# 3_Proxy.net
KiCad netlist of a schematic drawn in Altium Designer
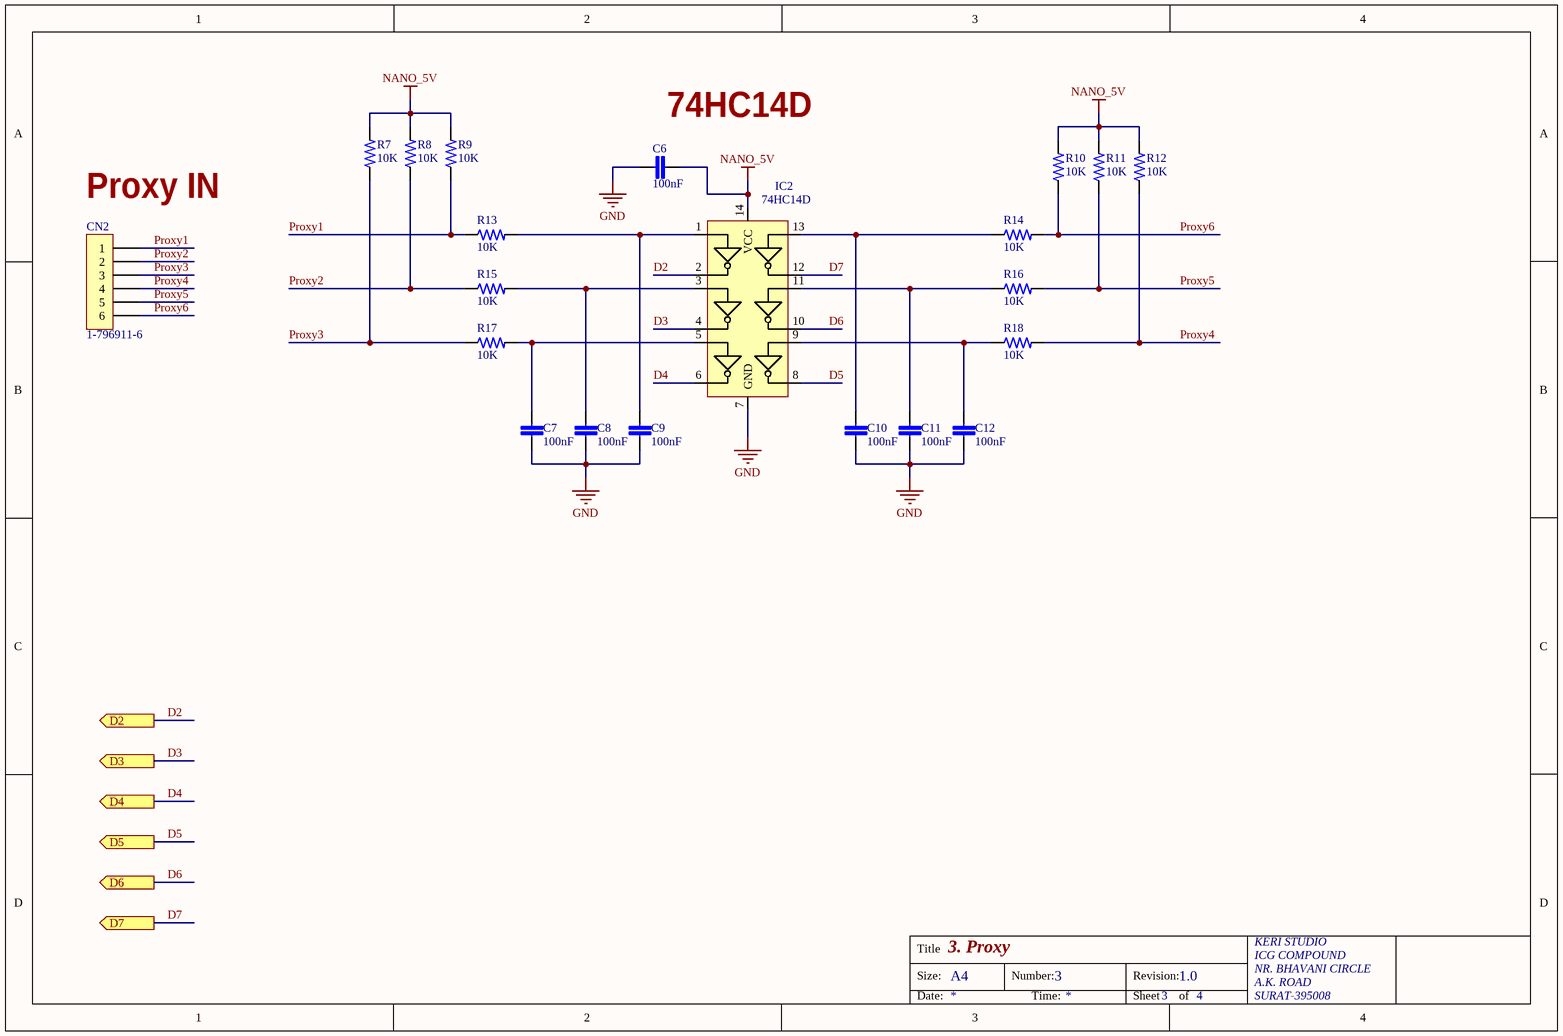
[diagram p0: 3. Proxy.SchDoc]

(export (version "E")
  (design (tool "Eeschema 10.0.6"))
  (components
    (comp (ref "C6")
      (value "100nF")
      (footprint "C0805")
      (description "Multilayer Ceramic Capacitors MLCC - SMD/SMT 0805 0.1uF 50volts X7R 20%")
      (fields
        (field (name "MANUFACTURER") "Murata")
        (field (name "MANUFACTURER PART NUMBER") "GCJ21BR71H104MA01L")
      )
      (libsource (lib "") (part "C_0805_0.1uF_1"))
    )
    (comp (ref "C7")
      (value "100nF")
      (footprint "C0805")
      (description "Multilayer Ceramic Capacitors MLCC - SMD/SMT 0805 0.1uF 50volts X7R 20%")
      (fields
        (field (name "MANUFACTURER") "Murata")
        (field (name "MANUFACTURER PART NUMBER") "GCJ21BR71H104MA01L")
      )
      (libsource (lib "keri_lib") (part "C_0805_0.1uF"))
    )
    (comp (ref "C8")
      (value "100nF")
      (footprint "C0805")
      (description "Multilayer Ceramic Capacitors MLCC - SMD/SMT 0805 0.1uF 50volts X7R 20%")
      (fields
        (field (name "MANUFACTURER") "Murata")
        (field (name "MANUFACTURER PART NUMBER") "GCJ21BR71H104MA01L")
      )
      (libsource (lib "keri_lib") (part "C_0805_0.1uF"))
    )
    (comp (ref "C9")
      (value "100nF")
      (footprint "C0805")
      (description "Multilayer Ceramic Capacitors MLCC - SMD/SMT 0805 0.1uF 50volts X7R 20%")
      (fields
        (field (name "MANUFACTURER") "Murata")
        (field (name "MANUFACTURER PART NUMBER") "GCJ21BR71H104MA01L")
      )
      (libsource (lib "keri_lib") (part "C_0805_0.1uF"))
    )
    (comp (ref "C10")
      (value "100nF")
      (footprint "C0805")
      (description "Multilayer Ceramic Capacitors MLCC - SMD/SMT 0805 0.1uF 50volts X7R 20%")
      (fields
        (field (name "MANUFACTURER") "Murata")
        (field (name "MANUFACTURER PART NUMBER") "GCJ21BR71H104MA01L")
      )
      (libsource (lib "keri_lib") (part "C_0805_0.1uF"))
    )
    (comp (ref "C11")
      (value "100nF")
      (footprint "C0805")
      (description "Multilayer Ceramic Capacitors MLCC - SMD/SMT 0805 0.1uF 50volts X7R 20%")
      (fields
        (field (name "MANUFACTURER") "Murata")
        (field (name "MANUFACTURER PART NUMBER") "GCJ21BR71H104MA01L")
      )
      (libsource (lib "keri_lib") (part "C_0805_0.1uF"))
    )
    (comp (ref "C12")
      (value "100nF")
      (footprint "C0805")
      (description "Multilayer Ceramic Capacitors MLCC - SMD/SMT 0805 0.1uF 50volts X7R 20%")
      (fields
        (field (name "MANUFACTURER") "Murata")
        (field (name "MANUFACTURER PART NUMBER") "GCJ21BR71H104MA01L")
      )
      (libsource (lib "keri_lib") (part "C_0805_0.1uF"))
    )
    (comp (ref "CN2")
      (value "1-796911-6")
      (footprint "Terminal_5.08mm_1X06")
      (description "Conn Terminal Block 16 POS 5mm Solder ST Thru-Hole")
      (fields (field (name "MANUFACTURER") "TE Connectivity") (field (name "VOLTAGE") "300V"))
      (libsource (lib "keri_lib") (part "Terminal_5.08mm_1X06"))
    )
    (comp (ref "IC2")
      (value "74HC14D")
      (footprint "SOIC-14")
      (description "IC, HEX INVERTER, SCHMITT TRIGGER SOIC14")
      (fields
        (field (name "MANUFACTURER") "NXP Semiconductors")
        (field (name "MANUFACTURER PART NUMBER") "74HC14D,653")
      )
      (libsource (lib "keri_lib") (part "74HC14D"))
    )
    (comp (ref "R7")
      (value "10K")
      (footprint "R0805")
      (description "Thick Film Resistors - SMD 10K 0805 5%")
      (fields (field (name "MANUFACTURER") "Bourns") (field (name "TOLERANCE") "5%"))
      (libsource (lib "keri_lib") (part "R_0805_10K"))
    )
    (comp (ref "R8")
      (value "10K")
      (footprint "R0805")
      (description "Thick Film Resistors - SMD 10K 0805 5%")
      (fields (field (name "MANUFACTURER") "Bourns") (field (name "TOLERANCE") "5%"))
      (libsource (lib "keri_lib") (part "R_0805_10K"))
    )
    (comp (ref "R9")
      (value "10K")
      (footprint "R0805")
      (description "Thick Film Resistors - SMD 10K 0805 5%")
      (fields (field (name "MANUFACTURER") "Bourns") (field (name "TOLERANCE") "5%"))
      (libsource (lib "keri_lib") (part "R_0805_10K"))
    )
    (comp (ref "R10")
      (value "10K")
      (footprint "R0805")
      (description "Thick Film Resistors - SMD 10K 0805 5%")
      (fields (field (name "MANUFACTURER") "Bourns") (field (name "TOLERANCE") "5%"))
      (libsource (lib "keri_lib") (part "R_0805_10K"))
    )
    (comp (ref "R11")
      (value "10K")
      (footprint "R0805")
      (description "Thick Film Resistors - SMD 10K 0805 5%")
      (fields (field (name "MANUFACTURER") "Bourns") (field (name "TOLERANCE") "5%"))
      (libsource (lib "keri_lib") (part "R_0805_10K"))
    )
    (comp (ref "R12")
      (value "10K")
      (footprint "R0805")
      (description "Thick Film Resistors - SMD 10K 0805 5%")
      (fields (field (name "MANUFACTURER") "Bourns") (field (name "TOLERANCE") "5%"))
      (libsource (lib "keri_lib") (part "R_0805_10K"))
    )
    (comp (ref "R13")
      (value "10K")
      (footprint "R0805")
      (description "Thick Film Resistors - SMD 10K 0805 5%")
      (fields (field (name "MANUFACTURER") "Bourns") (field (name "TOLERANCE") "5%"))
      (libsource (lib "keri_lib") (part "R_0805_10K"))
    )
    (comp (ref "R14")
      (value "10K")
      (footprint "R0805")
      (description "Thick Film Resistors - SMD 10K 0805 5%")
      (fields (field (name "MANUFACTURER") "Bourns") (field (name "TOLERANCE") "5%"))
      (libsource (lib "keri_lib") (part "R_0805_10K"))
    )
    (comp (ref "R15")
      (value "10K")
      (footprint "R0805")
      (description "Thick Film Resistors - SMD 10K 0805 5%")
      (fields (field (name "MANUFACTURER") "Bourns") (field (name "TOLERANCE") "5%"))
      (libsource (lib "keri_lib") (part "R_0805_10K"))
    )
    (comp (ref "R16")
      (value "10K")
      (footprint "R0805")
      (description "Thick Film Resistors - SMD 10K 0805 5%")
      (fields (field (name "MANUFACTURER") "Bourns") (field (name "TOLERANCE") "5%"))
      (libsource (lib "keri_lib") (part "R_0805_10K"))
    )
    (comp (ref "R17")
      (value "10K")
      (footprint "R0805")
      (description "Thick Film Resistors - SMD 10K 0805 5%")
      (fields (field (name "MANUFACTURER") "Bourns") (field (name "TOLERANCE") "5%"))
      (libsource (lib "keri_lib") (part "R_0805_10K"))
    )
    (comp (ref "R18")
      (value "10K")
      (footprint "R0805")
      (description "Thick Film Resistors - SMD 10K 0805 5%")
      (fields (field (name "MANUFACTURER") "Bourns") (field (name "TOLERANCE") "5%"))
      (libsource (lib "keri_lib") (part "R_0805_10K"))
    )
  )
  (nets
    (net (code "1") (name "/D2") (class "Default")
      (node (ref "IC2") (pin "2") (pinfunction "1Y_2") (pintype "passive"))
    )
    (net (code "2") (name "/D3") (class "Default")
      (node (ref "IC2") (pin "4") (pinfunction "2Y_4") (pintype "passive"))
    )
    (net (code "3") (name "/D4") (class "Default")
      (node (ref "IC2") (pin "6") (pinfunction "3Y_6") (pintype "passive"))
    )
    (net (code "4") (name "/D5") (class "Default")
      (node (ref "IC2") (pin "8") (pinfunction "4Y_8") (pintype "passive"))
    )
    (net (code "5") (name "/D6") (class "Default")
      (node (ref "IC2") (pin "10") (pinfunction "5Y_10") (pintype "passive"))
    )
    (net (code "6") (name "/D7") (class "Default")
      (node (ref "IC2") (pin "12") (pinfunction "6Y_12") (pintype "passive"))
    )
    (net (code "7") (name "/Proxy1") (class "Default")
      (node (ref "CN2") (pin "1") (pinfunction "1_1") (pintype "passive"))
      (node (ref "R13") (pin "1") (pinfunction "1_1") (pintype "passive"))
      (node (ref "R9") (pin "1") (pinfunction "1_1") (pintype "passive"))
    )
    (net (code "8") (name "/Proxy2") (class "Default")
      (node (ref "CN2") (pin "2") (pinfunction "2_2") (pintype "passive"))
      (node (ref "R15") (pin "1") (pinfunction "1_1") (pintype "passive"))
      (node (ref "R8") (pin "1") (pinfunction "1_1") (pintype "passive"))
    )
    (net (code "9") (name "/Proxy3") (class "Default")
      (node (ref "CN2") (pin "3") (pinfunction "3_3") (pintype "passive"))
      (node (ref "R17") (pin "1") (pinfunction "1_1") (pintype "passive"))
      (node (ref "R7") (pin "1") (pinfunction "1_1") (pintype "passive"))
    )
    (net (code "10") (name "/Proxy4") (class "Default")
      (node (ref "CN2") (pin "4") (pinfunction "4_4") (pintype "passive"))
      (node (ref "R12") (pin "1") (pinfunction "1_1") (pintype "passive"))
      (node (ref "R18") (pin "2") (pinfunction "2_2") (pintype "passive"))
    )
    (net (code "11") (name "/Proxy5") (class "Default")
      (node (ref "CN2") (pin "5") (pinfunction "5_5") (pintype "passive"))
      (node (ref "R11") (pin "1") (pinfunction "1_1") (pintype "passive"))
      (node (ref "R16") (pin "2") (pinfunction "2_2") (pintype "passive"))
    )
    (net (code "12") (name "/Proxy6") (class "Default")
      (node (ref "CN2") (pin "6") (pinfunction "6_6") (pintype "passive"))
      (node (ref "R10") (pin "1") (pinfunction "1_1") (pintype "passive"))
      (node (ref "R14") (pin "2") (pinfunction "2_2") (pintype "passive"))
    )
    (net (code "13") (name "GND") (class "Default")
      (node (ref "C10") (pin "2") (pinfunction "2_2") (pintype "passive"))
      (node (ref "C11") (pin "2") (pinfunction "2_2") (pintype "passive"))
      (node (ref "C12") (pin "2") (pinfunction "2_2") (pintype "passive"))
      (node (ref "C6") (pin "2") (pinfunction "2_2") (pintype "passive"))
      (node (ref "C7") (pin "2") (pinfunction "2_2") (pintype "passive"))
      (node (ref "C8") (pin "2") (pinfunction "2_2") (pintype "passive"))
      (node (ref "C9") (pin "2") (pinfunction "2_2") (pintype "passive"))
      (node (ref "IC2") (pin "7") (pinfunction "GND_7") (pintype "passive"))
    )
    (net (code "14") (name "NANO_5V") (class "Default")
      (node (ref "C6") (pin "1") (pinfunction "1_1") (pintype "passive"))
      (node (ref "IC2") (pin "14") (pinfunction "VCC_14") (pintype "passive"))
      (node (ref "R10") (pin "2") (pinfunction "2_2") (pintype "passive"))
      (node (ref "R11") (pin "2") (pinfunction "2_2") (pintype "passive"))
      (node (ref "R12") (pin "2") (pinfunction "2_2") (pintype "passive"))
      (node (ref "R7") (pin "2") (pinfunction "2_2") (pintype "passive"))
      (node (ref "R8") (pin "2") (pinfunction "2_2") (pintype "passive"))
      (node (ref "R9") (pin "2") (pinfunction "2_2") (pintype "passive"))
    )
    (net (code "15") (name "Net-(IC2-1A)") (class "Default")
      (node (ref "C9") (pin "1") (pinfunction "1_1") (pintype "passive"))
      (node (ref "IC2") (pin "1") (pinfunction "1A_1") (pintype "passive"))
      (node (ref "R13") (pin "2") (pinfunction "2_2") (pintype "passive"))
    )
    (net (code "16") (name "Net-(IC2-2A)") (class "Default")
      (node (ref "C8") (pin "1") (pinfunction "1_1") (pintype "passive"))
      (node (ref "IC2") (pin "3") (pinfunction "2A_3") (pintype "passive"))
      (node (ref "R15") (pin "2") (pinfunction "2_2") (pintype "passive"))
    )
    (net (code "17") (name "Net-(IC2-3A)") (class "Default")
      (node (ref "C7") (pin "1") (pinfunction "1_1") (pintype "passive"))
      (node (ref "IC2") (pin "5") (pinfunction "3A_5") (pintype "passive"))
      (node (ref "R17") (pin "2") (pinfunction "2_2") (pintype "passive"))
    )
    (net (code "18") (name "Net-(IC2-4A)") (class "Default")
      (node (ref "C12") (pin "1") (pinfunction "1_1") (pintype "passive"))
      (node (ref "IC2") (pin "9") (pinfunction "4A_9") (pintype "passive"))
      (node (ref "R18") (pin "1") (pinfunction "1_1") (pintype "passive"))
    )
    (net (code "19") (name "Net-(IC2-5A)") (class "Default")
      (node (ref "C11") (pin "1") (pinfunction "1_1") (pintype "passive"))
      (node (ref "IC2") (pin "11") (pinfunction "5A_11") (pintype "passive"))
      (node (ref "R16") (pin "1") (pinfunction "1_1") (pintype "passive"))
    )
    (net (code "20") (name "Net-(IC2-6A)") (class "Default")
      (node (ref "C10") (pin "1") (pinfunction "1_1") (pintype "passive"))
      (node (ref "IC2") (pin "13") (pinfunction "6A_13") (pintype "passive"))
      (node (ref "R14") (pin "1") (pinfunction "1_1") (pintype "passive"))
    )
  )
)
